# Line-Detection.net
KiCad netlist of a schematic drawn in Altium Designer
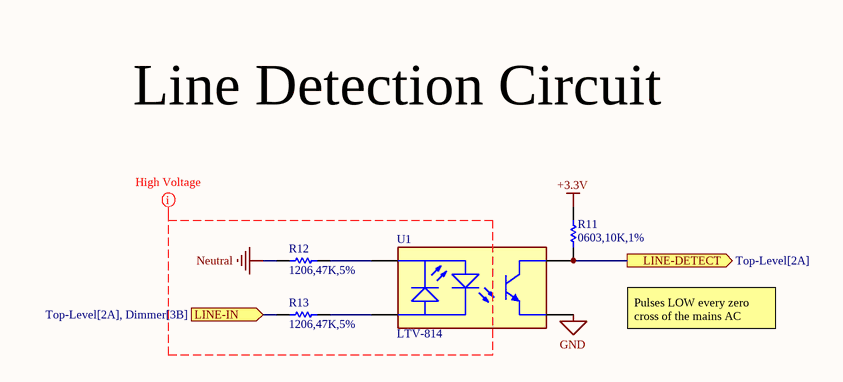
[diagram p0: Line-Detection.SchDoc]

(export (version "E")
  (design (tool "Eeschema 10.0.6"))
  (components
    (comp (ref "R11")
      (value "0603,10K,1%")
      (footprint "RESC1608X55N")
      (description "100mW Thick Film Resistor 75V ±100ppm/℃ ±1% 10kΩ 0603 Chip Resistor - Surface Mount ROHS")
      (fields
        (field (name "MANUFACTURER_PART_NUMBER") "RC0603FR-0710KL")
        (field (name "MOUSER PART NUMBER") "603-RC0603FR-0710KL")
      )
      (libsource (lib "LC-SchLib") (part "RC0603FR-0710KL"))
    )
    (comp (ref "R12")
      (value "1206,47K,5%")
      (footprint "RESC3116X65N")
      (description "500mW Thick Film Resistor ±5% ±200ppm/℃ 47kΩ 1206 Chip Resistor - Surface Mount ROHS")
      (fields (field (name "MP") "RC1206JR-070RL") (field (name "MF") "Yageo"))
      (libsource (lib "LC-SchLib") (part "RC1206JR-7W47KL"))
    )
    (comp (ref "R13")
      (value "1206,47K,5%")
      (footprint "RESC3116X65N")
      (description "500mW Thick Film Resistor ±5% ±200ppm/℃ 47kΩ 1206 Chip Resistor - Surface Mount ROHS")
      (fields (field (name "MP") "RC1206JR-070RL") (field (name "MF") "Yageo"))
      (libsource (lib "LC-SchLib") (part "RC1206JR-7W47KL"))
    )
    (comp (ref "U1")
      (value "LTV-814")
      (footprint "DIP-4_L6.5-W4.6-P2.54-LS7.6-BL")
      (description "35V 5kV 50mA 100mV@20mA,1mA 1 1.2V DC SMD-4P Transistor, Photovoltaic Output Optoisolators ROHS")
      (fields (field (name "LCSC PART NUMBER") "C10790"))
      (libsource (lib "LC-SchLib") (part "LTV-814"))
    )
  )
  (nets
    (net (code "1") (name "+3.3V") (class "Default")
      (node (ref "R11") (pin "2") (pinfunction "2_2") (pintype "passive"))
    )
    (net (code "2") (name "/LINE-DETECT") (class "Default")
      (node (ref "R11") (pin "1") (pinfunction "1_1") (pintype "passive"))
      (node (ref "U1") (pin "4") (pinfunction "Collector_4") (pintype "passive"))
    )
    (net (code "3") (name "/LINE-IN") (class "Default")
      (node (ref "R13") (pin "1") (pinfunction "1_1") (pintype "passive"))
    )
    (net (code "4") (name "GND") (class "Default")
      (node (ref "U1") (pin "3") (pinfunction "Emitter_3") (pintype "passive"))
    )
    (net (code "5") (name "Net-(R12-Pad2)") (class "Default")
      (node (ref "R12") (pin "2") (pinfunction "2_2") (pintype "passive"))
      (node (ref "U1") (pin "1") (pinfunction "Anode/Cathode_1") (pintype "passive"))
    )
    (net (code "6") (name "Net-(R13-Pad2)") (class "Default")
      (node (ref "R13") (pin "2") (pinfunction "2_2") (pintype "passive"))
      (node (ref "U1") (pin "2") (pinfunction "Anode/Cathode_2") (pintype "passive"))
    )
    (net (code "7") (name "Neutral") (class "Default")
      (node (ref "R12") (pin "1") (pinfunction "1_1") (pintype "passive"))
    )
  )
)
